# P-MT3620RDB-1-0_Dev.net
KiCad netlist of a schematic drawn in Altium Designer
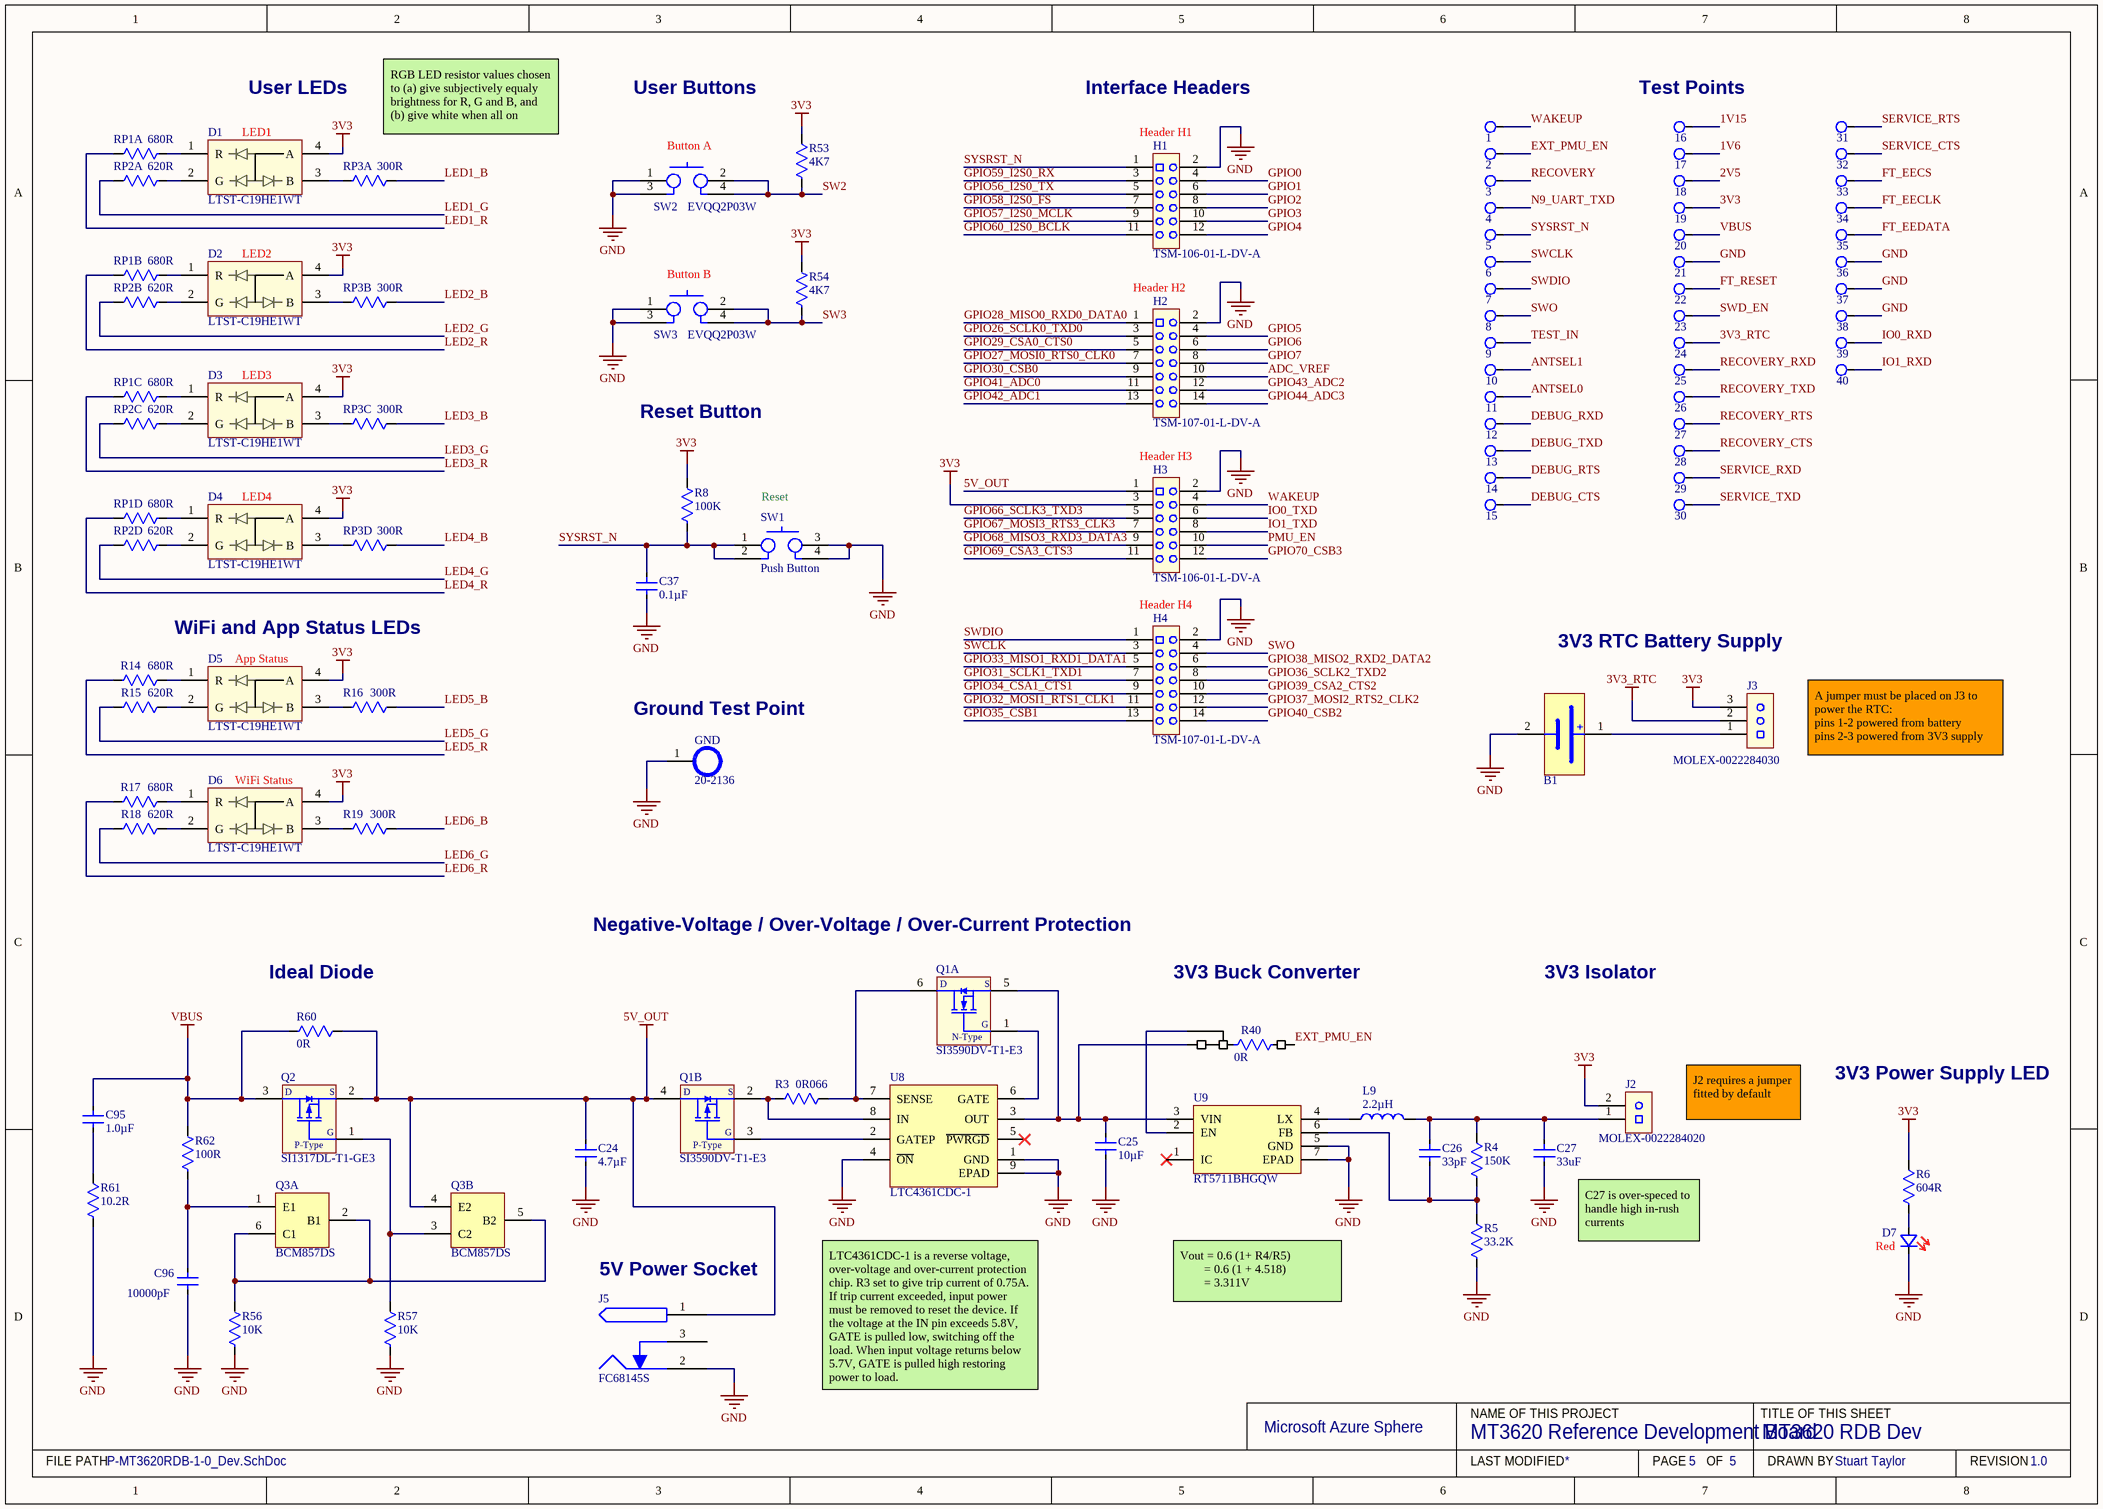
[diagram p0: P-MT3620RDB-1-0_Dev.SchDoc]

(export (version "E")
  (design (tool "Eeschema 10.0.6"))
  (components
    (comp (ref "1")
      (value "TestPoint")
      (footprint "Pad1.27mm")
      (description "Test Point")
      (libsource (lib "generic") (part "TestPoint"))
    )
    (comp (ref "2")
      (value "TestPoint")
      (footprint "Pad1.27mm")
      (description "Test Point")
      (libsource (lib "generic") (part "TestPoint"))
    )
    (comp (ref "3")
      (value "TestPoint")
      (footprint "Pad1.27mm")
      (description "Test Point")
      (libsource (lib "generic") (part "TestPoint"))
    )
    (comp (ref "4")
      (value "TestPoint")
      (footprint "Pad1.27mm")
      (description "Test Point")
      (libsource (lib "generic") (part "TestPoint"))
    )
    (comp (ref "5")
      (value "TestPoint")
      (footprint "Pad1.27mm")
      (description "Test Point")
      (libsource (lib "generic") (part "TestPoint"))
    )
    (comp (ref "6")
      (value "TestPoint")
      (footprint "Pad1.27mm")
      (description "Test Point")
      (libsource (lib "generic") (part "TestPoint"))
    )
    (comp (ref "7")
      (value "TestPoint")
      (footprint "Pad1.27mm")
      (description "Test Point")
      (libsource (lib "generic") (part "TestPoint"))
    )
    (comp (ref "8")
      (value "TestPoint")
      (footprint "Pad1.27mm")
      (description "Test Point")
      (libsource (lib "generic") (part "TestPoint"))
    )
    (comp (ref "9")
      (value "TestPoint")
      (footprint "Pad1.27mm")
      (description "Test Point")
      (libsource (lib "generic") (part "TestPoint"))
    )
    (comp (ref "10")
      (value "TestPoint")
      (footprint "Pad1.27mm")
      (description "Test Point")
      (libsource (lib "generic") (part "TestPoint"))
    )
    (comp (ref "11")
      (value "TestPoint")
      (footprint "Pad1.27mm")
      (description "Test Point")
      (libsource (lib "generic") (part "TestPoint"))
    )
    (comp (ref "12")
      (value "TestPoint")
      (footprint "Pad1.27mm")
      (description "Test Point")
      (libsource (lib "generic") (part "TestPoint"))
    )
    (comp (ref "13")
      (value "TestPoint")
      (footprint "Pad1.27mm")
      (description "Test Point")
      (libsource (lib "generic") (part "TestPoint"))
    )
    (comp (ref "14")
      (value "TestPoint")
      (footprint "Pad1.27mm")
      (description "Test Point")
      (libsource (lib "generic") (part "TestPoint"))
    )
    (comp (ref "15")
      (value "TestPoint")
      (footprint "Pad1.27mm")
      (description "Test Point")
      (libsource (lib "generic") (part "TestPoint"))
    )
    (comp (ref "16")
      (value "TestPoint")
      (footprint "Pad1.27mm")
      (description "Test Point")
      (libsource (lib "generic") (part "TestPoint"))
    )
    (comp (ref "17")
      (value "TestPoint")
      (footprint "Pad1.27mm")
      (description "Test Point")
      (libsource (lib "generic") (part "TestPoint"))
    )
    (comp (ref "18")
      (value "TestPoint")
      (footprint "Pad1.27mm")
      (description "Test Point")
      (libsource (lib "generic") (part "TestPoint"))
    )
    (comp (ref "19")
      (value "TestPoint")
      (footprint "Pad1.27mm")
      (description "Test Point")
      (libsource (lib "generic") (part "TestPoint"))
    )
    (comp (ref "20")
      (value "TestPoint")
      (footprint "Pad1.27mm")
      (description "Test Point")
      (libsource (lib "generic") (part "TestPoint"))
    )
    (comp (ref "21")
      (value "TestPoint")
      (footprint "Pad1.27mm")
      (description "Test Point")
      (libsource (lib "generic") (part "TestPoint"))
    )
    (comp (ref "22")
      (value "TestPoint")
      (footprint "Pad1.27mm")
      (description "Test Point")
      (libsource (lib "generic") (part "TestPoint"))
    )
    (comp (ref "23")
      (value "TestPoint")
      (footprint "Pad1.27mm")
      (description "Test Point")
      (libsource (lib "generic") (part "TestPoint"))
    )
    (comp (ref "24")
      (value "TestPoint")
      (footprint "Pad1.27mm")
      (description "Test Point")
      (libsource (lib "generic") (part "TestPoint"))
    )
    (comp (ref "25")
      (value "TestPoint")
      (footprint "Pad1.27mm")
      (description "Test Point")
      (libsource (lib "generic") (part "TestPoint"))
    )
    (comp (ref "26")
      (value "TestPoint")
      (footprint "Pad1.27mm")
      (description "Test Point")
      (libsource (lib "generic") (part "TestPoint"))
    )
    (comp (ref "27")
      (value "TestPoint")
      (footprint "Pad1.27mm")
      (description "Test Point")
      (libsource (lib "generic") (part "TestPoint"))
    )
    (comp (ref "28")
      (value "TestPoint")
      (footprint "Pad1.27mm")
      (description "Test Point")
      (libsource (lib "generic") (part "TestPoint"))
    )
    (comp (ref "29")
      (value "TestPoint")
      (footprint "Pad1.27mm")
      (description "Test Point")
      (libsource (lib "generic") (part "TestPoint"))
    )
    (comp (ref "30")
      (value "TestPoint")
      (footprint "Pad1.27mm")
      (description "Test Point")
      (libsource (lib "generic") (part "TestPoint"))
    )
    (comp (ref "31")
      (value "TestPoint")
      (footprint "Pad1.27mm")
      (description "Test Point")
      (libsource (lib "generic") (part "TestPoint"))
    )
    (comp (ref "32")
      (value "TestPoint")
      (footprint "Pad1.27mm")
      (description "Test Point")
      (libsource (lib "generic") (part "TestPoint"))
    )
    (comp (ref "33")
      (value "TestPoint")
      (footprint "Pad1.27mm")
      (description "Test Point")
      (libsource (lib "generic") (part "TestPoint"))
    )
    (comp (ref "34")
      (value "TestPoint")
      (footprint "Pad1.27mm")
      (description "Test Point")
      (libsource (lib "generic") (part "TestPoint"))
    )
    (comp (ref "35")
      (value "TestPoint")
      (footprint "Pad1.27mm")
      (description "Test Point")
      (libsource (lib "generic") (part "TestPoint"))
    )
    (comp (ref "36")
      (value "TestPoint")
      (footprint "Pad1.27mm")
      (description "Test Point")
      (libsource (lib "generic") (part "TestPoint"))
    )
    (comp (ref "37")
      (value "TestPoint")
      (footprint "Pad1.27mm")
      (description "Test Point")
      (libsource (lib "generic") (part "TestPoint"))
    )
    (comp (ref "38")
      (value "TestPoint")
      (footprint "Pad1.27mm")
      (description "Test Point")
      (libsource (lib "generic") (part "TestPoint"))
    )
    (comp (ref "39")
      (value "TestPoint")
      (footprint "Pad1.27mm")
      (description "Test Point")
      (libsource (lib "generic") (part "TestPoint"))
    )
    (comp (ref "40")
      (value "TestPoint")
      (footprint "Pad1.27mm")
      (description "Test Point")
      (libsource (lib "generic") (part "TestPoint"))
    )
    (comp (ref "B1")
      (value "HARWIN-S8421-45R")
      (footprint "HARWIN-S8421-45R")
      (description "SMT CR2032 coin cell holder")
      (fields (field (name "MANUFACTURER") "HARWIN") (field (name "MANUFACTURER PART NUMBER") "S8421-45R"))
      (libsource (lib "Harwin") (part "HARWIN-S8421-45R"))
    )
    (comp (ref "C24")
      (value "4.7µF")
      (footprint "CAPC1005-EIA0402 0.55MM MED")
      (description "CAP CER 4.7UF 10V 10% X5R 0402")
      (fields
        (field (name "MANUFACTURER") "TDK Corporation")
        (field (name "MANUFACTURER PART NUMBER") "C1005X5R1A475K050BC")
        (field (name "CAPACITANCE") "4.7µF")
      )
      (libsource (lib "TDK_Capacitor_C_0402") (part "4.7µF 0402 X5R 10V"))
    )
    (comp (ref "C25")
      (value "10µF")
      (footprint "CAPC1608-EIA0603-1MM-MED")
      (description "CAP CER 10UF 25V 20% X5R 0603")
      (fields
        (field (name "MANUFACTURER") "TDK Corporation")
        (field (name "MANUFACTURER PART NUMBER") "C1608X5R1E106M080AC")
        (field (name "CAPACITANCE") "10µF")
      )
      (libsource (lib "TDK-Capacitor_C_0603") (part "10µF 0603 X5R 25V"))
    )
    (comp (ref "C26")
      (value "33pF")
      (footprint "CAPC1005-EIA0402 0.55MM MED")
      (description "CAP CER 33PF 50V 5% NP0 0402")
      (fields
        (field (name "MANUFACTURER") "TDK Corporation")
        (field (name "MANUFACTURER PART NUMBER") "C1005C0G1H330J050BA")
        (field (name "CAPACITANCE") "33pF")
      )
      (libsource (lib "TDK_Capacitor_C_0402") (part "33pF 0402 C0G, NP0 50V"))
    )
    (comp (ref "C27")
      (value "33uF")
      (footprint "TDK_0805")
      (description "CAP CER 33UF 6.3V X5R 0805")
      (fields
        (field (name "MANUFACTURER") "TDK")
        (field (name "MANUFACTURER PART NUMBER") "C2012X5R0J336M125AC")
      )
      (libsource (lib "TDK_Capacitor_C_0805") (part "33uF 0805 X5R 6.3V"))
    )
    (comp (ref "C37")
      (value "0.1µF")
      (footprint "CAPC1005-EIA0402 0.55MM MED")
      (description "CAP CER 0.1UF 50V 10% X7R 0402")
      (fields
        (field (name "MANUFACTURER") "TDK Corporation")
        (field (name "MANUFACTURER PART NUMBER") "C1005X7R1H104K050BB")
        (field (name "CAPACITANCE") "0.1µF")
      )
      (libsource (lib "TDK_Capacitor_C_0402") (part "0.1µF 0402 X7R 50V"))
    )
    (comp (ref "C95")
      (value "1.0µF")
      (footprint "CAPC1005-EIA0402 0.55MM MED")
      (description "CAP CER 1UF 35V 10% X5R 0402")
      (fields
        (field (name "MANUFACTURER") "TDK Corporation")
        (field (name "MANUFACTURER PART NUMBER") "C1005X5R1V105K050BC")
        (field (name "CAPACITANCE") "1.0µF")
      )
      (libsource (lib "TDK_Capacitor_C_0402") (part "1.0µF 0402 X5R 35V"))
    )
    (comp (ref "C96")
      (value "10000pF")
      (footprint "CAPC1005-EIA0402 0.55MM MED")
      (description "CAP CER 10000PF 50V 10% X7R 0402")
      (fields
        (field (name "MANUFACTURER") "TDK Corporation")
        (field (name "MANUFACTURER PART NUMBER") "C1005X7R1H103K050BB")
        (field (name "CAPACITANCE") "10000pF")
      )
      (libsource (lib "TDK_Capacitor_C_0402") (part "10000pF 0402 X7R 50V"))
    )
    (comp (ref "D1")
      (value "LTST-C19HE1WT")
      (footprint "LTST-C19HE1WT")
      (description "LED RGB DIFFUSED 0606 SMD")
      (fields (field (name "MANUFACTURER") "Lite-On Inc."))
      (libsource (lib "Lite-On") (part "LTST-C19HE1WT"))
    )
    (comp (ref "D2")
      (value "LTST-C19HE1WT")
      (footprint "LTST-C19HE1WT")
      (description "LED RGB DIFFUSED 0606 SMD")
      (fields (field (name "MANUFACTURER") "Lite-On Inc."))
      (libsource (lib "Lite-On") (part "LTST-C19HE1WT"))
    )
    (comp (ref "D3")
      (value "LTST-C19HE1WT")
      (footprint "LTST-C19HE1WT")
      (description "LED RGB DIFFUSED 0606 SMD")
      (fields (field (name "MANUFACTURER") "Lite-On Inc."))
      (libsource (lib "Lite-On") (part "LTST-C19HE1WT"))
    )
    (comp (ref "D4")
      (value "LTST-C19HE1WT")
      (footprint "LTST-C19HE1WT")
      (description "LED RGB DIFFUSED 0606 SMD")
      (fields (field (name "MANUFACTURER") "Lite-On Inc."))
      (libsource (lib "Lite-On") (part "LTST-C19HE1WT"))
    )
    (comp (ref "D5")
      (value "LTST-C19HE1WT")
      (footprint "LTST-C19HE1WT")
      (description "LED RGB DIFFUSED 0606 SMD")
      (fields (field (name "MANUFACTURER") "Lite-On Inc."))
      (libsource (lib "Lite-On") (part "LTST-C19HE1WT"))
    )
    (comp (ref "D6")
      (value "LTST-C19HE1WT")
      (footprint "LTST-C19HE1WT")
      (description "LED RGB DIFFUSED 0606 SMD")
      (fields (field (name "MANUFACTURER") "Lite-On Inc."))
      (libsource (lib "Lite-On") (part "LTST-C19HE1WT"))
    )
    (comp (ref "D7")
      (value "Red LED")
      (footprint "Rohm SML-D12 Red")
      (description "1.6 x 0.8 x 0.55mm (0603) LED 620nm Red")
      (fields
        (field (name "MANUFACTURER") "Rohm Semiconductor")
        (field (name "MANUFACTURER PART NUMBER") "SML-D12U8WT86")
        (field (name "COLOUR") "Red")
      )
      (libsource (lib "Rohm") (part "SML-D12U"))
    )
    (comp (ref "GND")
      (value "20-2136")
      (footprint "20-2136")
      (description "VERO - 20-2136 - TERMINAL, PCB, BLACK, PK100")
      (fields (field (name "MANUFACTURER") "VERO"))
      (libsource (lib "Vero") (part "20-2136"))
    )
    (comp (ref "H1")
      (value "TSM-106-01-L-DV-A")
      (footprint "TSM-106-01-L-DV-A")
      (description "CONN HEADER 12POS .100\" SMD GOLD")
      (fields (field (name "MANUFACTURER") "Samtec"))
      (libsource (lib "Samtec") (part "TSM-106-01-L-DV-A"))
    )
    (comp (ref "H2")
      (value "TSM-107-01-L-DV-A")
      (footprint "TSM-107-01-L-DV-A")
      (description "CONN HEADER 14POS .100\" SMD GOLD")
      (fields (field (name "MANUFACTURER") "Samtec"))
      (libsource (lib "Samtec") (part "TSM-107-01-L-DV-A"))
    )
    (comp (ref "H3")
      (value "TSM-106-01-L-DV-A")
      (footprint "TSM-106-01-L-DV-A")
      (description "CONN HEADER 12POS .100\" SMD GOLD")
      (fields (field (name "MANUFACTURER") "Samtec"))
      (libsource (lib "Samtec") (part "TSM-106-01-L-DV-A"))
    )
    (comp (ref "H4")
      (value "TSM-107-01-L-DV-A")
      (footprint "TSM-107-01-L-DV-A")
      (description "CONN HEADER 14POS .100\" SMD GOLD")
      (fields (field (name "MANUFACTURER") "Samtec"))
      (libsource (lib "Samtec") (part "TSM-107-01-L-DV-A"))
    )
    (comp (ref "J2")
      (value "MOLEX-0022284020")
      (footprint "0022284020")
      (description "CONN HEADER 2POS .100 VERT TIN")
      (fields
        (field (name "MANUFACTURER") "Molex, LLC")
        (field (name "MANUFACTURER PART NUMBER") "0022284020")
      )
      (libsource (lib "Molex") (part "MOLEX-0022284020"))
    )
    (comp (ref "J3")
      (value "MOLEX-0022284030")
      (footprint "0022284030")
      (description "CONN HEADER 3POS .100 VERT TIN")
      (fields
        (field (name "MANUFACTURER") "Molex, LLC")
        (field (name "MANUFACTURER PART NUMBER") "0022284030")
      )
      (libsource (lib "Molex") (part "MOLEX-0022284030"))
    )
    (comp (ref "J5")
      (value "FC68145S")
      (footprint "FC68145S")
      (description "CLIFF ELECTRONIC COMPONENTS, FC68145S, DC Power Connector, Jack, 1 A, 1.3 mm, Surface Mount")
      (fields (field (name "MANUFACTURER") "Cliff"))
      (libsource (lib "Cliff") (part "FC68145S"))
    )
    (comp (ref "L9")
      (value "2.2µH")
      (footprint "NR3015T2R2M")
      (description "FIXED IND 2.2UH 1.5A 72 MOHM SMD")
      (fields
        (field (name "MANUFACTURER") "Taiyo Yuden")
        (field (name "MANUFACTURER PART NUMBER") "NR3015T2R2M")
      )
      (libsource (lib "TaiyoYuden ") (part "NR3015T2R2M"))
    )
    (comp (ref "Q1")
      (value "SI3590DV-T1-E3")
      (footprint "SI3590DV-T1-E3")
      (description "MOSFET N&P-CH 30V (D-S)")
      (fields (field (name "MANUFACTURER") "Vishay Siliconix"))
      (libsource (lib "Vishay") (part "SI3590DV-T1-E3"))
    )
    (comp (ref "Q2")
      (value "SI1317DL-T1-GE3")
      (footprint "VISHAY_SOT-323")
      (description "VISHAY SI1317DL-T1-GE3 MOSFET Transistor, P Channel, -1.4 A, -20 V, 0.125 ohm, -4.5 V, 450 mV")
      (fields (field (name "MANUFACTURER") "Vishay Siliconix"))
      (libsource (lib "Vishay") (part "SI1317DL-T1-GE3"))
    )
    (comp (ref "Q3")
      (value "BCM857DS")
      (footprint "NXP-SOT457")
      (description "BJT ARRAY, DUAL PNP, -45V, -100MA, 6-SOT-457")
      (fields
        (field (name "MANUFACTURER") "NXP Semiconductors")
        (field (name "MANUFACTURER PART NUMBER") "BCM857DS,115")
      )
      (libsource (lib "NXP") (part "BCM857DS,115"))
    )
    (comp (ref "R3")
      (value "0R066")
      (footprint "VISHAY-0603")
      (description "Current Sense Resistors - SMD .4watt .066ohm 1%")
      (fields
        (field (name "MANUFACTURER") "Vishay Dale")
        (field (name "MANUFACTURER PART NUMBER") "WSLP0603R0660FEB")
      )
      (libsource (lib "Vishay") (part "WSLP0603R0660FEB"))
    )
    (comp (ref "R4")
      (value "150K")
      (footprint "RES 0402 MEDIUM DENSITY")
      (description "RES 150K OHM 1/10W 1% 0402 SMD")
      (fields
        (field (name "MANUFACTURER") "Panasonic Electronic Components")
        (field (name "MANUFACTURER PART NUMBER") "ERJ-2RKF1503X")
        (field (name "RESISTANCE (OHMS)") "150K")
      )
      (libsource (lib "Panasonic_Resistor_ERJ2R") (part "150K"))
    )
    (comp (ref "R5")
      (value "33.2K")
      (footprint "RES 0402 MEDIUM DENSITY")
      (description "RES 33.2K OHM 1/10W 1% 0402 SMD")
      (fields
        (field (name "MANUFACTURER") "Panasonic Electronic Components")
        (field (name "MANUFACTURER PART NUMBER") "ERJ-2RKF3322X")
        (field (name "RESISTANCE (OHMS)") "33.2K")
      )
      (libsource (lib "Panasonic_Resistor_ERJ2R") (part "33.2K"))
    )
    (comp (ref "R6")
      (value "604R")
      (footprint "RES 0402 MEDIUM DENSITY")
      (description "RES 604 OHM 1/10W 1% 0402 SMD")
      (fields
        (field (name "MANUFACTURER") "Panasonic Electronic Components")
        (field (name "MANUFACTURER PART NUMBER") "ERJ-2RKF6040X")
        (field (name "RESISTANCE (OHMS)") "604R")
      )
      (libsource (lib "Panasonic_Resistor_ERJ2R") (part "604R"))
    )
    (comp (ref "R8")
      (value "100K")
      (footprint "RES 0402 MEDIUM DENSITY")
      (description "RES 100K OHM 1/10W 1% 0402 SMD")
      (fields
        (field (name "MANUFACTURER") "Panasonic Electronic Components")
        (field (name "MANUFACTURER PART NUMBER") "ERJ-2RKF1003X")
        (field (name "RESISTANCE (OHMS)") "100K")
      )
      (libsource (lib "Panasonic_Resistor_ERJ2R") (part "100K"))
    )
    (comp (ref "R14")
      (value "680R")
      (footprint "RES 0402 MEDIUM DENSITY")
      (description "RES 680 OHM 1/10W 1% 0402 SMD")
      (fields
        (field (name "MANUFACTURER") "Panasonic Electronic Components")
        (field (name "MANUFACTURER PART NUMBER") "ERJ-2RKF6800X")
        (field (name "RESISTANCE (OHMS)") "680R")
      )
      (libsource (lib "Panasonic_Resistor_ERJ2R") (part "680R"))
    )
    (comp (ref "R15")
      (value "620R")
      (footprint "RES 0402 MEDIUM DENSITY")
      (description "RES 620 OHM 1/10W 1% 0402 SMD")
      (fields
        (field (name "MANUFACTURER") "Panasonic Electronic Components")
        (field (name "MANUFACTURER PART NUMBER") "ERJ-2RKF6200X")
        (field (name "RESISTANCE (OHMS)") "620R")
      )
      (libsource (lib "Panasonic_Resistor_ERJ2R") (part "620R"))
    )
    (comp (ref "R16")
      (value "300R")
      (footprint "RES 0402 MEDIUM DENSITY")
      (description "RES 300 OHM 1/10W 1% 0402 SMD")
      (fields
        (field (name "MANUFACTURER") "Panasonic Electronic Components")
        (field (name "MANUFACTURER PART NUMBER") "ERJ-2RKF3000X")
        (field (name "RESISTANCE (OHMS)") "300R")
      )
      (libsource (lib "Panasonic_Resistor_ERJ2R") (part "300R"))
    )
    (comp (ref "R17")
      (value "680R")
      (footprint "RES 0402 MEDIUM DENSITY")
      (description "RES 680 OHM 1/10W 1% 0402 SMD")
      (fields
        (field (name "MANUFACTURER") "Panasonic Electronic Components")
        (field (name "MANUFACTURER PART NUMBER") "ERJ-2RKF6800X")
        (field (name "RESISTANCE (OHMS)") "680R")
      )
      (libsource (lib "Panasonic_Resistor_ERJ2R") (part "680R"))
    )
    (comp (ref "R18")
      (value "620R")
      (footprint "RES 0402 MEDIUM DENSITY")
      (description "RES 620 OHM 1/10W 1% 0402 SMD")
      (fields
        (field (name "MANUFACTURER") "Panasonic Electronic Components")
        (field (name "MANUFACTURER PART NUMBER") "ERJ-2RKF6200X")
        (field (name "RESISTANCE (OHMS)") "620R")
      )
      (libsource (lib "Panasonic_Resistor_ERJ2R") (part "620R"))
    )
    (comp (ref "R19")
      (value "300R")
      (footprint "RES 0402 MEDIUM DENSITY")
      (description "RES 300 OHM 1/10W 1% 0402 SMD")
      (fields
        (field (name "MANUFACTURER") "Panasonic Electronic Components")
        (field (name "MANUFACTURER PART NUMBER") "ERJ-2RKF3000X")
        (field (name "RESISTANCE (OHMS)") "300R")
      )
      (libsource (lib "Panasonic_Resistor_ERJ2R") (part "300R"))
    )
    (comp (ref "R40")
      (value "0R")
      (footprint "THREE-WAY-0402-WITH-SHORT")
      (description "RES SMD 0.0OHM JUMPER 1/10W 0402")
      (fields
        (field (name "MANUFACTURER") "Panasonic Electronic Components")
        (field (name "MANUFACTURER PART NUMBER") "ERJ-2GE0R00X")
      )
      (libsource (lib "generic-res") (part "THREE-WAY-0R-0402"))
    )
    (comp (ref "R53")
      (value "4K7")
      (footprint "RES 0402 MEDIUM DENSITY")
      (description "RES 4.7K OHM 1/10W 1% 0402 SMD")
      (fields
        (field (name "MANUFACTURER") "Panasonic Electronic Components")
        (field (name "MANUFACTURER PART NUMBER") "ERJ-2RKF4701X")
        (field (name "RESISTANCE (OHMS)") "4K7")
      )
      (libsource (lib "Panasonic_Resistor_ERJ2R") (part "4.7K"))
    )
    (comp (ref "R54")
      (value "4K7")
      (footprint "RES 0402 MEDIUM DENSITY")
      (description "RES 4.7K OHM 1/10W 1% 0402 SMD")
      (fields
        (field (name "MANUFACTURER") "Panasonic Electronic Components")
        (field (name "MANUFACTURER PART NUMBER") "ERJ-2RKF4701X")
        (field (name "RESISTANCE (OHMS)") "4K7")
      )
      (libsource (lib "Panasonic_Resistor_ERJ2R") (part "4.7K"))
    )
    (comp (ref "R56")
      (value "10K")
      (footprint "RES 0402 MEDIUM DENSITY")
      (description "RES 10K OHM 1/10W 1% 0402 SMD")
      (fields
        (field (name "MANUFACTURER") "Panasonic Electronic Components")
        (field (name "MANUFACTURER PART NUMBER") "ERJ-2RKF1002X")
        (field (name "RESISTANCE (OHMS)") "10K")
      )
      (libsource (lib "Panasonic_Resistor_ERJ2R") (part "10K"))
    )
    (comp (ref "R57")
      (value "10K")
      (footprint "RES 0402 MEDIUM DENSITY")
      (description "RES 10K OHM 1/10W 1% 0402 SMD")
      (fields
        (field (name "MANUFACTURER") "Panasonic Electronic Components")
        (field (name "MANUFACTURER PART NUMBER") "ERJ-2RKF1002X")
        (field (name "RESISTANCE (OHMS)") "10K")
      )
      (libsource (lib "Panasonic_Resistor_ERJ2R") (part "10K"))
    )
    (comp (ref "R60")
      (value "0R")
      (footprint "RES 0402 MEDIUM DENSITY")
      (description "RES 0.0 OHM 1/10W JUMP 0402 SMD")
      (fields
        (field (name "MANUFACTURER") "Panasonic Electronic Components")
        (field (name "MANUFACTURER PART NUMBER") "ERJ-2GE0R00X")
        (field (name "RESISTANCE (OHMS)") "0R")
      )
      (libsource (lib "Panasonic_Resistor_ERJ2R") (part "0R"))
    )
    (comp (ref "R61")
      (value "10.2R")
      (footprint "RES 0402 MEDIUM DENSITY")
      (description "RES 10.2 OHM 1/10W 1% 0402 SMD")
      (fields
        (field (name "MANUFACTURER") "Panasonic Electronic Components")
        (field (name "MANUFACTURER PART NUMBER") "ERJ-2RKF10R2X")
        (field (name "RESISTANCE (OHMS)") "10.2R")
      )
      (libsource (lib "Panasonic_Resistor_ERJ2R") (part "10.2R"))
    )
    (comp (ref "R62")
      (value "100R")
      (footprint "RES 0402 MEDIUM DENSITY")
      (description "RES 100 OHM 1/10W 1% 0402 SMD")
      (fields
        (field (name "MANUFACTURER") "Panasonic Electronic Components")
        (field (name "MANUFACTURER PART NUMBER") "ERJ-2RKF1000X")
        (field (name "RESISTANCE (OHMS)") "100R")
      )
      (libsource (lib "Panasonic_Resistor_ERJ2R") (part "100R"))
    )
    (comp (ref "RP1")
      (value "680R")
      (footprint "EXB-N8V")
      (fields
        (field (name "MANUFACTURER") "Panasonic / Panasonic ECG")
        (field (name "MANUFACTURER PART NUMBER") "EXB-N8V681JX")
      )
      (libsource (lib "Panasonic") (part "EXB-N8V681JX"))
    )
    (comp (ref "RP2")
      (value "620R")
      (footprint "EXB-N8V")
      (fields
        (field (name "MANUFACTURER") "Panasonic ECG")
        (field (name "MANUFACTURER PART NUMBER") "EXB-N8V621JX")
        (field (name "TOLERANCE") "5%")
      )
      (libsource (lib "Panasonic") (part "EXB-N8V621JX"))
    )
    (comp (ref "RP3")
      (value "300R")
      (footprint "EXB-N8V")
      (fields
        (field (name "MANUFACTURER") "Panasonic / Panasonic ECG")
        (field (name "MANUFACTURER PART NUMBER") "EXB-N8V301JX")
        (field (name "TOLERANCE") "5%")
      )
      (libsource (lib "Panasonic") (part "EXB-N8V301JX"))
    )
    (comp (ref "SW1")
      (value "Push Button")
      (footprint "DHT-1158")
      (libsource (lib "Seeed") (part "DHT-1158"))
    )
    (comp (ref "SW2")
      (value "SWI TACT SPN0 PANASONIC EVQQ2P03W")
      (footprint "EVQQ2P03W")
      (description "PANASONIC - EVQQ2P03W - SWITCH, SPNO, SMD")
      (fields (field (name "MANUFACTURER") "PANASONIC") (field (name "MANUFACTURER PART NUMBER") "EVQQ2P03W"))
      (libsource (lib "switch") (part "SWI TACT SPN0 PANASONIC EVQQ2P03W"))
    )
    (comp (ref "SW3")
      (value "SWI TACT SPN0 PANASONIC EVQQ2P03W")
      (footprint "EVQQ2P03W")
      (description "PANASONIC - EVQQ2P03W - SWITCH, SPNO, SMD")
      (fields (field (name "MANUFACTURER") "PANASONIC") (field (name "MANUFACTURER PART NUMBER") "EVQQ2P03W"))
      (libsource (lib "switch") (part "SWI TACT SPN0 PANASONIC EVQQ2P03W"))
    )
    (comp (ref "U8")
      (value "LTC4361CDC-1")
      (footprint "LTC4361-1#TRPBF")
      (description "LINEAR TECHNOLOGY LTC4361CDC-1#TRMPBF IC, OVERVOLTAGE/CUR PROT, 8DFN")
      (fields
        (field (name "MANUFACTURER") "Linear Technology")
        (field (name "MANUFACTURER PART NUMBER") "LTC4361CDC-1#TRMPBF")
      )
      (libsource (lib "LinearTech") (part "LTC4361CDC-1#TRMPBF"))
    )
    (comp (ref "U9")
      (value "RT5711BHGQW")
      (footprint "SON65P200X80_HS-7N")
      (fields (field (name "MANUFACTURER") "Richtek"))
      (libsource (lib "Richtek") (part "RT5711BHGQW"))
    )
  )
  (nets
    (net (code "1") (name "/1V6") (class "Default")
      (node (ref "17") (pin "1") (pinfunction "1_1") (pintype "passive"))
    )
    (net (code "2") (name "/1V15") (class "Default")
      (node (ref "16") (pin "1") (pinfunction "1_1") (pintype "passive"))
    )
    (net (code "3") (name "/2V5") (class "Default")
      (node (ref "18") (pin "1") (pinfunction "1_1") (pintype "passive"))
    )
    (net (code "4") (name "/ADC_VREF") (class "Default")
      (node (ref "H2") (pin "10") (pinfunction "10_10") (pintype "passive"))
    )
    (net (code "5") (name "/ANTSEL0") (class "Default")
      (node (ref "11") (pin "1") (pinfunction "1_1") (pintype "passive"))
    )
    (net (code "6") (name "/ANTSEL1") (class "Default")
      (node (ref "10") (pin "1") (pinfunction "1_1") (pintype "passive"))
    )
    (net (code "7") (name "/DEBUG_CTS") (class "Default")
      (node (ref "15") (pin "1") (pinfunction "1_1") (pintype "passive"))
    )
    (net (code "8") (name "/DEBUG_RTS") (class "Default")
      (node (ref "14") (pin "1") (pinfunction "1_1") (pintype "passive"))
    )
    (net (code "9") (name "/DEBUG_RXD") (class "Default")
      (node (ref "12") (pin "1") (pinfunction "1_1") (pintype "passive"))
    )
    (net (code "10") (name "/DEBUG_TXD") (class "Default")
      (node (ref "13") (pin "1") (pinfunction "1_1") (pintype "passive"))
    )
    (net (code "11") (name "/EXT_PMU_EN") (class "Default")
      (node (ref "2") (pin "1") (pinfunction "1_1") (pintype "passive"))
      (node (ref "R40") (pin "1") (pinfunction "1_1") (pintype "passive"))
    )
    (net (code "12") (name "/FT_EECLK") (class "Default")
      (node (ref "34") (pin "1") (pinfunction "1_1") (pintype "passive"))
    )
    (net (code "13") (name "/FT_EECS") (class "Default")
      (node (ref "33") (pin "1") (pinfunction "1_1") (pintype "passive"))
    )
    (net (code "14") (name "/FT_EEDATA") (class "Default")
      (node (ref "35") (pin "1") (pinfunction "1_1") (pintype "passive"))
    )
    (net (code "15") (name "/FT_RESET") (class "Default")
      (node (ref "22") (pin "1") (pinfunction "1_1") (pintype "passive"))
    )
    (net (code "16") (name "/GPIO0") (class "Default")
      (node (ref "H1") (pin "4") (pinfunction "4_4") (pintype "passive"))
    )
    (net (code "17") (name "/GPIO1") (class "Default")
      (node (ref "H1") (pin "6") (pinfunction "6_6") (pintype "passive"))
    )
    (net (code "18") (name "/GPIO2") (class "Default")
      (node (ref "H1") (pin "8") (pinfunction "8_8") (pintype "passive"))
    )
    (net (code "19") (name "/GPIO3") (class "Default")
      (node (ref "H1") (pin "10") (pinfunction "10_10") (pintype "passive"))
    )
    (net (code "20") (name "/GPIO4") (class "Default")
      (node (ref "H1") (pin "12") (pinfunction "12_12") (pintype "passive"))
    )
    (net (code "21") (name "/GPIO5") (class "Default")
      (node (ref "H2") (pin "4") (pinfunction "4_4") (pintype "passive"))
    )
    (net (code "22") (name "/GPIO6") (class "Default")
      (node (ref "H2") (pin "6") (pinfunction "6_6") (pintype "passive"))
    )
    (net (code "23") (name "/GPIO7") (class "Default")
      (node (ref "H2") (pin "8") (pinfunction "8_8") (pintype "passive"))
    )
    (net (code "24") (name "/GPIO26_SCLK0_TXD0") (class "Default")
      (node (ref "H2") (pin "3") (pinfunction "3_3") (pintype "passive"))
    )
    (net (code "25") (name "/GPIO27_MOSI0_RTS0_CLK0") (class "Default")
      (node (ref "H2") (pin "7") (pinfunction "7_7") (pintype "passive"))
    )
    (net (code "26") (name "/GPIO28_MISO0_RXD0_DATA0") (class "Default")
      (node (ref "H2") (pin "1") (pinfunction "1_1") (pintype "passive"))
    )
    (net (code "27") (name "/GPIO29_CSA0_CTS0") (class "Default")
      (node (ref "H2") (pin "5") (pinfunction "5_5") (pintype "passive"))
    )
    (net (code "28") (name "/GPIO30_CSB0") (class "Default")
      (node (ref "H2") (pin "9") (pinfunction "9_9") (pintype "passive"))
    )
    (net (code "29") (name "/GPIO31_SCLK1_TXD1") (class "Default")
      (node (ref "H4") (pin "7") (pinfunction "7_7") (pintype "passive"))
    )
    (net (code "30") (name "/GPIO32_MOSI1_RTS1_CLK1") (class "Default")
      (node (ref "H4") (pin "11") (pinfunction "11_11") (pintype "passive"))
    )
    (net (code "31") (name "/GPIO33_MISO1_RXD1_DATA1") (class "Default")
      (node (ref "H4") (pin "5") (pinfunction "5_5") (pintype "passive"))
    )
    (net (code "32") (name "/GPIO34_CSA1_CTS1") (class "Default")
      (node (ref "H4") (pin "9") (pinfunction "9_9") (pintype "passive"))
    )
    (net (code "33") (name "/GPIO35_CSB1") (class "Default")
      (node (ref "H4") (pin "13") (pinfunction "13_13") (pintype "passive"))
    )
    (net (code "34") (name "/GPIO36_SCLK2_TXD2") (class "Default")
      (node (ref "H4") (pin "8") (pinfunction "8_8") (pintype "passive"))
    )
    (net (code "35") (name "/GPIO37_MOSI2_RTS2_CLK2") (class "Default")
      (node (ref "H4") (pin "12") (pinfunction "12_12") (pintype "passive"))
    )
    (net (code "36") (name "/GPIO38_MISO2_RXD2_DATA2") (class "Default")
      (node (ref "H4") (pin "6") (pinfunction "6_6") (pintype "passive"))
    )
    (net (code "37") (name "/GPIO39_CSA2_CTS2") (class "Default")
      (node (ref "H4") (pin "10") (pinfunction "10_10") (pintype "passive"))
    )
    (net (code "38") (name "/GPIO40_CSB2") (class "Default")
      (node (ref "H4") (pin "14") (pinfunction "14_14") (pintype "passive"))
    )
    (net (code "39") (name "/GPIO41_ADC0") (class "Default")
      (node (ref "H2") (pin "11") (pinfunction "11_11") (pintype "passive"))
    )
    (net (code "40") (name "/GPIO42_ADC1") (class "Default")
      (node (ref "H2") (pin "13") (pinfunction "13_13") (pintype "passive"))
    )
    (net (code "41") (name "/GPIO43_ADC2") (class "Default")
      (node (ref "H2") (pin "12") (pinfunction "12_12") (pintype "passive"))
    )
    (net (code "42") (name "/GPIO44_ADC3") (class "Default")
      (node (ref "H2") (pin "14") (pinfunction "14_14") (pintype "passive"))
    )
    (net (code "43") (name "/GPIO56_I2S0_TX") (class "Default")
      (node (ref "H1") (pin "5") (pinfunction "5_5") (pintype "passive"))
    )
    (net (code "44") (name "/GPIO57_I2S0_MCLK") (class "Default")
      (node (ref "H1") (pin "9") (pinfunction "9_9") (pintype "passive"))
    )
    (net (code "45") (name "/GPIO58_I2S0_FS") (class "Default")
      (node (ref "H1") (pin "7") (pinfunction "7_7") (pintype "passive"))
    )
    (net (code "46") (name "/GPIO59_I2S0_RX") (class "Default")
      (node (ref "H1") (pin "3") (pinfunction "3_3") (pintype "passive"))
    )
    (net (code "47") (name "/GPIO60_I2S0_BCLK") (class "Default")
      (node (ref "H1") (pin "11") (pinfunction "11_11") (pintype "passive"))
    )
    (net (code "48") (name "/GPIO66_SCLK3_TXD3") (class "Default")
      (node (ref "H3") (pin "5") (pinfunction "5_5") (pintype "passive"))
    )
    (net (code "49") (name "/GPIO67_MOSI3_RTS3_CLK3") (class "Default")
      (node (ref "H3") (pin "7") (pinfunction "7_7") (pintype "passive"))
    )
    (net (code "50") (name "/GPIO68_MISO3_RXD3_DATA3") (class "Default")
      (node (ref "H3") (pin "9") (pinfunction "9_9") (pintype "passive"))
    )
    (net (code "51") (name "/GPIO69_CSA3_CTS3") (class "Default")
      (node (ref "H3") (pin "11") (pinfunction "11_11") (pintype "passive"))
    )
    (net (code "52") (name "/GPIO70_CSB3") (class "Default")
      (node (ref "H3") (pin "12") (pinfunction "12_12") (pintype "passive"))
    )
    (net (code "53") (name "/IO0_RXD") (class "Default")
      (node (ref "39") (pin "1") (pinfunction "1_1") (pintype "passive"))
    )
    (net (code "54") (name "/IO0_TXD") (class "Default")
      (node (ref "H3") (pin "6") (pinfunction "6_6") (pintype "passive"))
    )
    (net (code "55") (name "/IO1_RXD") (class "Default")
      (node (ref "40") (pin "1") (pinfunction "1_1") (pintype "passive"))
    )
    (net (code "56") (name "/IO1_TXD") (class "Default")
      (node (ref "H3") (pin "8") (pinfunction "8_8") (pintype "passive"))
    )
    (net (code "57") (name "/LED1_B") (class "Default")
      (node (ref "RP3") (pin "2") (pinfunction "2_2") (pintype "passive"))
    )
    (net (code "58") (name "/LED1_G") (class "Default")
      (node (ref "RP2") (pin "2") (pinfunction "2_2") (pintype "passive"))
    )
    (net (code "59") (name "/LED1_R") (class "Default")
      (node (ref "RP1") (pin "2") (pinfunction "2_2") (pintype "passive"))
    )
    (net (code "60") (name "/LED2_B") (class "Default")
      (node (ref "RP3") (pin "4") (pinfunction "4_4") (pintype "passive"))
    )
    (net (code "61") (name "/LED2_G") (class "Default")
      (node (ref "RP2") (pin "4") (pinfunction "4_4") (pintype "passive"))
    )
    (net (code "62") (name "/LED2_R") (class "Default")
      (node (ref "RP1") (pin "4") (pinfunction "4_4") (pintype "passive"))
    )
    (net (code "63") (name "/LED3_B") (class "Default")
      (node (ref "RP3") (pin "6") (pinfunction "6_6") (pintype "passive"))
    )
    (net (code "64") (name "/LED3_G") (class "Default")
      (node (ref "RP2") (pin "6") (pinfunction "6_6") (pintype "passive"))
    )
    (net (code "65") (name "/LED3_R") (class "Default")
      (node (ref "RP1") (pin "6") (pinfunction "6_6") (pintype "passive"))
    )
    (net (code "66") (name "/LED4_B") (class "Default")
      (node (ref "RP3") (pin "8") (pinfunction "8_8") (pintype "passive"))
    )
    (net (code "67") (name "/LED4_G") (class "Default")
      (node (ref "RP2") (pin "8") (pinfunction "8_8") (pintype "passive"))
    )
    (net (code "68") (name "/LED4_R") (class "Default")
      (node (ref "RP1") (pin "8") (pinfunction "8_8") (pintype "passive"))
    )
    (net (code "69") (name "/LED5_B") (class "Default")
      (node (ref "R16") (pin "1") (pinfunction "1_1") (pintype "passive"))
    )
    (net (code "70") (name "/LED5_G") (class "Default")
      (node (ref "R15") (pin "2") (pinfunction "2_2") (pintype "passive"))
    )
    (net (code "71") (name "/LED5_R") (class "Default")
      (node (ref "R14") (pin "2") (pinfunction "2_2") (pintype "passive"))
    )
    (net (code "72") (name "/LED6_B") (class "Default")
      (node (ref "R19") (pin "1") (pinfunction "1_1") (pintype "passive"))
    )
    (net (code "73") (name "/LED6_G") (class "Default")
      (node (ref "R18") (pin "2") (pinfunction "2_2") (pintype "passive"))
    )
    (net (code "74") (name "/LED6_R") (class "Default")
      (node (ref "R17") (pin "2") (pinfunction "2_2") (pintype "passive"))
    )
    (net (code "75") (name "/N9_UART_TXD") (class "Default")
      (node (ref "4") (pin "1") (pinfunction "1_1") (pintype "passive"))
    )
    (net (code "76") (name "/PMU_EN") (class "Default")
      (node (ref "H3") (pin "10") (pinfunction "10_10") (pintype "passive"))
    )
    (net (code "77") (name "/RECOVERY") (class "Default")
      (node (ref "3") (pin "1") (pinfunction "1_1") (pintype "passive"))
    )
    (net (code "78") (name "/RECOVERY_CTS") (class "Default")
      (node (ref "28") (pin "1") (pinfunction "1_1") (pintype "passive"))
    )
    (net (code "79") (name "/RECOVERY_RTS") (class "Default")
      (node (ref "27") (pin "1") (pinfunction "1_1") (pintype "passive"))
    )
    (net (code "80") (name "/RECOVERY_RXD") (class "Default")
      (node (ref "25") (pin "1") (pinfunction "1_1") (pintype "passive"))
    )
    (net (code "81") (name "/RECOVERY_TXD") (class "Default")
      (node (ref "26") (pin "1") (pinfunction "1_1") (pintype "passive"))
    )
    (net (code "82") (name "/SERVICE_CTS") (class "Default")
      (node (ref "32") (pin "1") (pinfunction "1_1") (pintype "passive"))
    )
    (net (code "83") (name "/SERVICE_RTS") (class "Default")
      (node (ref "31") (pin "1") (pinfunction "1_1") (pintype "passive"))
    )
    (net (code "84") (name "/SERVICE_RXD") (class "Default")
      (node (ref "29") (pin "1") (pinfunction "1_1") (pintype "passive"))
    )
    (net (code "85") (name "/SERVICE_TXD") (class "Default")
      (node (ref "30") (pin "1") (pinfunction "1_1") (pintype "passive"))
    )
    (net (code "86") (name "/SW2") (class "Default")
      (node (ref "R53") (pin "2") (pinfunction "2_2") (pintype "passive"))
      (node (ref "SW2") (pin "2") (pinfunction "2_2") (pintype "passive"))
      (node (ref "SW2") (pin "4") (pinfunction "4_4") (pintype "passive"))
    )
    (net (code "87") (name "/SW3") (class "Default")
      (node (ref "R54") (pin "2") (pinfunction "2_2") (pintype "passive"))
      (node (ref "SW3") (pin "2") (pinfunction "2_2") (pintype "passive"))
      (node (ref "SW3") (pin "4") (pinfunction "4_4") (pintype "passive"))
    )
    (net (code "88") (name "/SWCLK") (class "Default")
      (node (ref "6") (pin "1") (pinfunction "1_1") (pintype "passive"))
      (node (ref "H4") (pin "3") (pinfunction "3_3") (pintype "passive"))
    )
    (net (code "89") (name "/SWDIO") (class "Default")
      (node (ref "7") (pin "1") (pinfunction "1_1") (pintype "passive"))
      (node (ref "H4") (pin "1") (pinfunction "1_1") (pintype "passive"))
    )
    (net (code "90") (name "/SWD_EN") (class "Default")
      (node (ref "23") (pin "1") (pinfunction "1_1") (pintype "passive"))
    )
    (net (code "91") (name "/SWO") (class "Default")
      (node (ref "8") (pin "1") (pinfunction "1_1") (pintype "passive"))
      (node (ref "H4") (pin "4") (pinfunction "4_4") (pintype "passive"))
    )
    (net (code "92") (name "/SYSRST_N") (class "Default")
      (node (ref "5") (pin "1") (pinfunction "1_1") (pintype "passive"))
      (node (ref "C37") (pin "2") (pinfunction "2_2") (pintype "passive"))
      (node (ref "H1") (pin "1") (pinfunction "1_1") (pintype "passive"))
      (node (ref "R8") (pin "2") (pinfunction "2_2") (pintype "passive"))
      (node (ref "SW1") (pin "1") (pinfunction "1_1") (pintype "passive"))
      (node (ref "SW1") (pin "2") (pinfunction "2_2") (pintype "passive"))
    )
    (net (code "93") (name "/TEST_IN") (class "Default")
      (node (ref "9") (pin "1") (pinfunction "1_1") (pintype "passive"))
    )
    (net (code "94") (name "/WAKEUP") (class "Default")
      (node (ref "1") (pin "1") (pinfunction "1_1") (pintype "passive"))
      (node (ref "H3") (pin "4") (pinfunction "4_4") (pintype "passive"))
    )
    (net (code "95") (name "3V3") (class "Default")
      (node (ref "19") (pin "1") (pinfunction "1_1") (pintype "passive"))
      (node (ref "D1") (pin "4") (pinfunction "A_4") (pintype "passive"))
      (node (ref "D2") (pin "4") (pinfunction "A_4") (pintype "passive"))
      (node (ref "D3") (pin "4") (pinfunction "A_4") (pintype "passive"))
      (node (ref "D4") (pin "4") (pinfunction "A_4") (pintype "passive"))
      (node (ref "D5") (pin "4") (pinfunction "A_4") (pintype "passive"))
      (node (ref "D6") (pin "4") (pinfunction "A_4") (pintype "passive"))
      (node (ref "H3") (pin "3") (pinfunction "3_3") (pintype "passive"))
      (node (ref "J2") (pin "2") (pinfunction "2_2") (pintype "passive"))
      (node (ref "J3") (pin "3") (pinfunction "3_3") (pintype "passive"))
      (node (ref "R53") (pin "1") (pinfunction "1_1") (pintype "passive"))
      (node (ref "R54") (pin "1") (pinfunction "1_1") (pintype "passive"))
      (node (ref "R6") (pin "1") (pinfunction "1_1") (pintype "passive"))
      (node (ref "R8") (pin "1") (pinfunction "1_1") (pintype "passive"))
    )
    (net (code "96") (name "3V3_RTC") (class "Default")
      (node (ref "24") (pin "1") (pinfunction "1_1") (pintype "passive"))
      (node (ref "J3") (pin "2") (pinfunction "2_2") (pintype "passive"))
    )
    (net (code "97") (name "5V_OUT") (class "Default")
      (node (ref "C24") (pin "2") (pinfunction "2_2") (pintype "passive"))
      (node (ref "H3") (pin "1") (pinfunction "1_1") (pintype "passive"))
      (node (ref "J5") (pin "1") (pinfunction "1_1") (pintype "passive"))
      (node (ref "Q1") (pin "4") (pinfunction "D2_4") (pintype "passive"))
      (node (ref "Q2") (pin "2") (pinfunction "S_2") (pintype "passive"))
      (node (ref "Q3") (pin "4") (pinfunction "E2_4") (pintype "passive"))
      (node (ref "R60") (pin "1") (pinfunction "1_1") (pintype "passive"))
    )
    (net (code "98") (name "GND") (class "Default")
      (node (ref "21") (pin "1") (pinfunction "1_1") (pintype "passive"))
      (node (ref "36") (pin "1") (pinfunction "1_1") (pintype "passive"))
      (node (ref "37") (pin "1") (pinfunction "1_1") (pintype "passive"))
      (node (ref "38") (pin "1") (pinfunction "1_1") (pintype "passive"))
      (node (ref "B1") (pin "2") (pinfunction "-_2") (pintype "passive"))
      (node (ref "C24") (pin "1") (pinfunction "1_1") (pintype "passive"))
      (node (ref "C25") (pin "1") (pinfunction "1_1") (pintype "passive"))
      (node (ref "C27") (pin "1") (pinfunction "1_1") (pintype "passive"))
      (node (ref "C37") (pin "1") (pinfunction "1_1") (pintype "passive"))
      (node (ref "C96") (pin "1") (pinfunction "1_1") (pintype "passive"))
      (node (ref "D7") (pin "1") (pinfunction "K_1") (pintype "passive"))
      (node (ref "GND") (pin "1") (pinfunction "1_1") (pintype "passive"))
      (node (ref "H1") (pin "2") (pinfunction "2_2") (pintype "passive"))
      (node (ref "H2") (pin "2") (pinfunction "2_2") (pintype "passive"))
      (node (ref "H3") (pin "2") (pinfunction "2_2") (pintype "passive"))
      (node (ref "H4") (pin "2") (pinfunction "2_2") (pintype "passive"))
      (node (ref "J5") (pin "2") (pinfunction "2_2") (pintype "passive"))
      (node (ref "R5") (pin "2") (pinfunction "2_2") (pintype "passive"))
      (node (ref "R56") (pin "2") (pinfunction "2_2") (pintype "passive"))
      (node (ref "R57") (pin "2") (pinfunction "2_2") (pintype "passive"))
      (node (ref "R61") (pin "2") (pinfunction "2_2") (pintype "passive"))
      (node (ref "SW1") (pin "3") (pinfunction "3_3") (pintype "passive"))
      (node (ref "SW1") (pin "4") (pinfunction "4_4") (pintype "passive"))
      (node (ref "SW2") (pin "1") (pinfunction "1_1") (pintype "passive"))
      (node (ref "SW2") (pin "3") (pinfunction "3_3") (pintype "passive"))
      (node (ref "SW3") (pin "1") (pinfunction "1_1") (pintype "passive"))
      (node (ref "SW3") (pin "3") (pinfunction "3_3") (pintype "passive"))
      (node (ref "U8") (pin "1") (pinfunction "GND_1") (pintype "passive"))
      (node (ref "U8") (pin "4") (pinfunction "~{ON}_4") (pintype "passive"))
      (node (ref "U8") (pin "9") (pinfunction "EPAD_9") (pintype "passive"))
      (node (ref "U9") (pin "5") (pinfunction "GND_5") (pintype "passive"))
      (node (ref "U9") (pin "7") (pinfunction "EPAD_7") (pintype "passive"))
    )
    (net (code "99") (name "Net-(B1-+)") (class "Default")
      (node (ref "B1") (pin "1") (pinfunction "+_1") (pintype "passive"))
      (node (ref "J3") (pin "1") (pinfunction "1_1") (pintype "passive"))
    )
    (net (code "100") (name "Net-(C26-Pad2)") (class "Default")
      (node (ref "C26") (pin "2") (pinfunction "2_2") (pintype "passive"))
      (node (ref "C27") (pin "2") (pinfunction "2_2") (pintype "passive"))
      (node (ref "J2") (pin "1") (pinfunction "1_1") (pintype "passive"))
      (node (ref "L9") (pin "2") (pinfunction "2_2") (pintype "passive"))
      (node (ref "R4") (pin "1") (pinfunction "1_1") (pintype "passive"))
    )
    (net (code "101") (name "Net-(C95-Pad1)") (class "Default")
      (node (ref "C95") (pin "1") (pinfunction "1_1") (pintype "passive"))
      (node (ref "R61") (pin "1") (pinfunction "1_1") (pintype "passive"))
    )
    (net (code "102") (name "Net-(D1-B)") (class "Default")
      (node (ref "D1") (pin "3") (pinfunction "B_3") (pintype "passive"))
      (node (ref "RP3") (pin "1") (pinfunction "1_1") (pintype "passive"))
    )
    (net (code "103") (name "Net-(D1-G)") (class "Default")
      (node (ref "D1") (pin "2") (pinfunction "G_2") (pintype "passive"))
      (node (ref "RP2") (pin "1") (pinfunction "1_1") (pintype "passive"))
    )
    (net (code "104") (name "Net-(D1-R)") (class "Default")
      (node (ref "D1") (pin "1") (pinfunction "R_1") (pintype "passive"))
      (node (ref "RP1") (pin "1") (pinfunction "1_1") (pintype "passive"))
    )
    (net (code "105") (name "Net-(D2-B)") (class "Default")
      (node (ref "D2") (pin "3") (pinfunction "B_3") (pintype "passive"))
      (node (ref "RP3") (pin "3") (pinfunction "3_3") (pintype "passive"))
    )
    (net (code "106") (name "Net-(D2-G)") (class "Default")
      (node (ref "D2") (pin "2") (pinfunction "G_2") (pintype "passive"))
      (node (ref "RP2") (pin "3") (pinfunction "3_3") (pintype "passive"))
    )
    (net (code "107") (name "Net-(D2-R)") (class "Default")
      (node (ref "D2") (pin "1") (pinfunction "R_1") (pintype "passive"))
      (node (ref "RP1") (pin "3") (pinfunction "3_3") (pintype "passive"))
    )
    (net (code "108") (name "Net-(D3-B)") (class "Default")
      (node (ref "D3") (pin "3") (pinfunction "B_3") (pintype "passive"))
      (node (ref "RP3") (pin "5") (pinfunction "5_5") (pintype "passive"))
    )
    (net (code "109") (name "Net-(D3-G)") (class "Default")
      (node (ref "D3") (pin "2") (pinfunction "G_2") (pintype "passive"))
      (node (ref "RP2") (pin "5") (pinfunction "5_5") (pintype "passive"))
    )
    (net (code "110") (name "Net-(D3-R)") (class "Default")
      (node (ref "D3") (pin "1") (pinfunction "R_1") (pintype "passive"))
      (node (ref "RP1") (pin "5") (pinfunction "5_5") (pintype "passive"))
    )
    (net (code "111") (name "Net-(D4-B)") (class "Default")
      (node (ref "D4") (pin "3") (pinfunction "B_3") (pintype "passive"))
      (node (ref "RP3") (pin "7") (pinfunction "7_7") (pintype "passive"))
    )
    (net (code "112") (name "Net-(D4-G)") (class "Default")
      (node (ref "D4") (pin "2") (pinfunction "G_2") (pintype "passive"))
      (node (ref "RP2") (pin "7") (pinfunction "7_7") (pintype "passive"))
    )
    (net (code "113") (name "Net-(D4-R)") (class "Default")
      (node (ref "D4") (pin "1") (pinfunction "R_1") (pintype "passive"))
      (node (ref "RP1") (pin "7") (pinfunction "7_7") (pintype "passive"))
    )
    (net (code "114") (name "Net-(D5-B)") (class "Default")
      (node (ref "D5") (pin "3") (pinfunction "B_3") (pintype "passive"))
      (node (ref "R16") (pin "2") (pinfunction "2_2") (pintype "passive"))
    )
    (net (code "115") (name "Net-(D5-G)") (class "Default")
      (node (ref "D5") (pin "2") (pinfunction "G_2") (pintype "passive"))
      (node (ref "R15") (pin "1") (pinfunction "1_1") (pintype "passive"))
    )
    (net (code "116") (name "Net-(D5-R)") (class "Default")
      (node (ref "D5") (pin "1") (pinfunction "R_1") (pintype "passive"))
      (node (ref "R14") (pin "1") (pinfunction "1_1") (pintype "passive"))
    )
    (net (code "117") (name "Net-(D6-B)") (class "Default")
      (node (ref "D6") (pin "3") (pinfunction "B_3") (pintype "passive"))
      (node (ref "R19") (pin "2") (pinfunction "2_2") (pintype "passive"))
    )
    (net (code "118") (name "Net-(D6-G)") (class "Default")
      (node (ref "D6") (pin "2") (pinfunction "G_2") (pintype "passive"))
      (node (ref "R18") (pin "1") (pinfunction "1_1") (pintype "passive"))
    )
    (net (code "119") (name "Net-(D6-R)") (class "Default")
      (node (ref "D6") (pin "1") (pinfunction "R_1") (pintype "passive"))
      (node (ref "R17") (pin "1") (pinfunction "1_1") (pintype "passive"))
    )
    (net (code "120") (name "Net-(D7-A)") (class "Default")
      (node (ref "D7") (pin "2") (pinfunction "A_2") (pintype "passive"))
      (node (ref "R6") (pin "2") (pinfunction "2_2") (pintype "passive"))
    )
    (net (code "121") (name "Net-(Q1A-D1)") (class "Default")
      (node (ref "Q1") (pin "6") (pinfunction "D1_6") (pintype "passive"))
      (node (ref "R3") (pin "1") (pinfunction "1_1") (pintype "passive"))
      (node (ref "U8") (pin "7") (pinfunction "SENSE_7") (pintype "passive"))
    )
    (net (code "122") (name "Net-(Q1A-G1)") (class "Default")
      (node (ref "Q1") (pin "1") (pinfunction "G1_1") (pintype "passive"))
      (node (ref "U8") (pin "6") (pinfunction "GATE_6") (pintype "passive"))
    )
    (net (code "123") (name "Net-(Q1A-S1)") (class "Default")
      (node (ref "C25") (pin "2") (pinfunction "2_2") (pintype "passive"))
      (node (ref "Q1") (pin "5") (pinfunction "S1_5") (pintype "passive"))
      (node (ref "R40") (pin "3") (pinfunction "3_3") (pintype "passive"))
      (node (ref "U8") (pin "3") (pinfunction "OUT_3") (pintype "passive"))
      (node (ref "U9") (pin "3") (pinfunction "VIN_3") (pintype "passive"))
    )
    (net (code "124") (name "Net-(Q1B-G2)") (class "Default")
      (node (ref "Q1") (pin "3") (pinfunction "G2_3") (pintype "passive"))
      (node (ref "U8") (pin "2") (pinfunction "GATEP_2") (pintype "passive"))
    )
    (net (code "125") (name "Net-(Q1B-S2)") (class "Default")
      (node (ref "Q1") (pin "2") (pinfunction "S2_2") (pintype "passive"))
      (node (ref "R3") (pin "2") (pinfunction "2_2") (pintype "passive"))
      (node (ref "U8") (pin "8") (pinfunction "IN_8") (pintype "passive"))
    )
    (net (code "126") (name "Net-(Q2-G)") (class "Default")
      (node (ref "Q2") (pin "1") (pinfunction "G_1") (pintype "passive"))
      (node (ref "Q3") (pin "3") (pinfunction "C2_3") (pintype "passive"))
      (node (ref "R57") (pin "1") (pinfunction "1_1") (pintype "passive"))
    )
    (net (code "127") (name "Net-(Q3A-B1)") (class "Default")
      (node (ref "Q3") (pin "2") (pinfunction "B1_2") (pintype "passive"))
      (node (ref "Q3") (pin "5") (pinfunction "B2_5") (pintype "passive"))
      (node (ref "Q3") (pin "6") (pinfunction "C1_6") (pintype "passive"))
      (node (ref "R56") (pin "1") (pinfunction "1_1") (pintype "passive"))
    )
    (net (code "128") (name "Net-(Q3A-E1)") (class "Default")
      (node (ref "C96") (pin "2") (pinfunction "2_2") (pintype "passive"))
      (node (ref "Q3") (pin "1") (pinfunction "E1_1") (pintype "passive"))
      (node (ref "R62") (pin "2") (pinfunction "2_2") (pintype "passive"))
    )
    (net (code "129") (name "Net-(U9-EN)") (class "Default")
      (node (ref "R40") (pin "2") (pinfunction "2_2") (pintype "passive"))
      (node (ref "U9") (pin "2") (pinfunction "EN_2") (pintype "passive"))
    )
    (net (code "130") (name "Net-(U9-FB)") (class "Default")
      (node (ref "C26") (pin "1") (pinfunction "1_1") (pintype "passive"))
      (node (ref "R4") (pin "2") (pinfunction "2_2") (pintype "passive"))
      (node (ref "R5") (pin "1") (pinfunction "1_1") (pintype "passive"))
      (node (ref "U9") (pin "6") (pinfunction "FB_6") (pintype "passive"))
    )
    (net (code "131") (name "Net-(U9-LX)") (class "Default")
      (node (ref "L9") (pin "1") (pinfunction "1_1") (pintype "passive"))
      (node (ref "U9") (pin "4") (pinfunction "LX_4") (pintype "passive"))
    )
    (net (code "132") (name "VBUS") (class "Default")
      (node (ref "20") (pin "1") (pinfunction "1_1") (pintype "passive"))
      (node (ref "C95") (pin "2") (pinfunction "2_2") (pintype "passive"))
      (node (ref "Q2") (pin "3") (pinfunction "D_3") (pintype "passive"))
      (node (ref "R60") (pin "2") (pinfunction "2_2") (pintype "passive"))
      (node (ref "R62") (pin "1") (pinfunction "1_1") (pintype "passive"))
    )
    (net (code "133") (name "unconnected-(J5-Pad3)") (class "Default")
      (node (ref "J5") (pin "3") (pinfunction "3_3") (pintype "passive"))
    )
    (net (code "134") (name "unconnected-(U8-~{PWRGD}-Pad5)") (class "Default")
      (node (ref "U8") (pin "5") (pinfunction "~{PWRGD}_5") (pintype "passive+no_connect"))
    )
    (net (code "135") (name "unconnected-(U9-IC-Pad1)") (class "Default")
      (node (ref "U9") (pin "1") (pinfunction "IC_1") (pintype "passive+no_connect"))
    )
  )
)
